# XcvrTestWiring.net
KiCad netlist of a schematic drawn in EAGLE
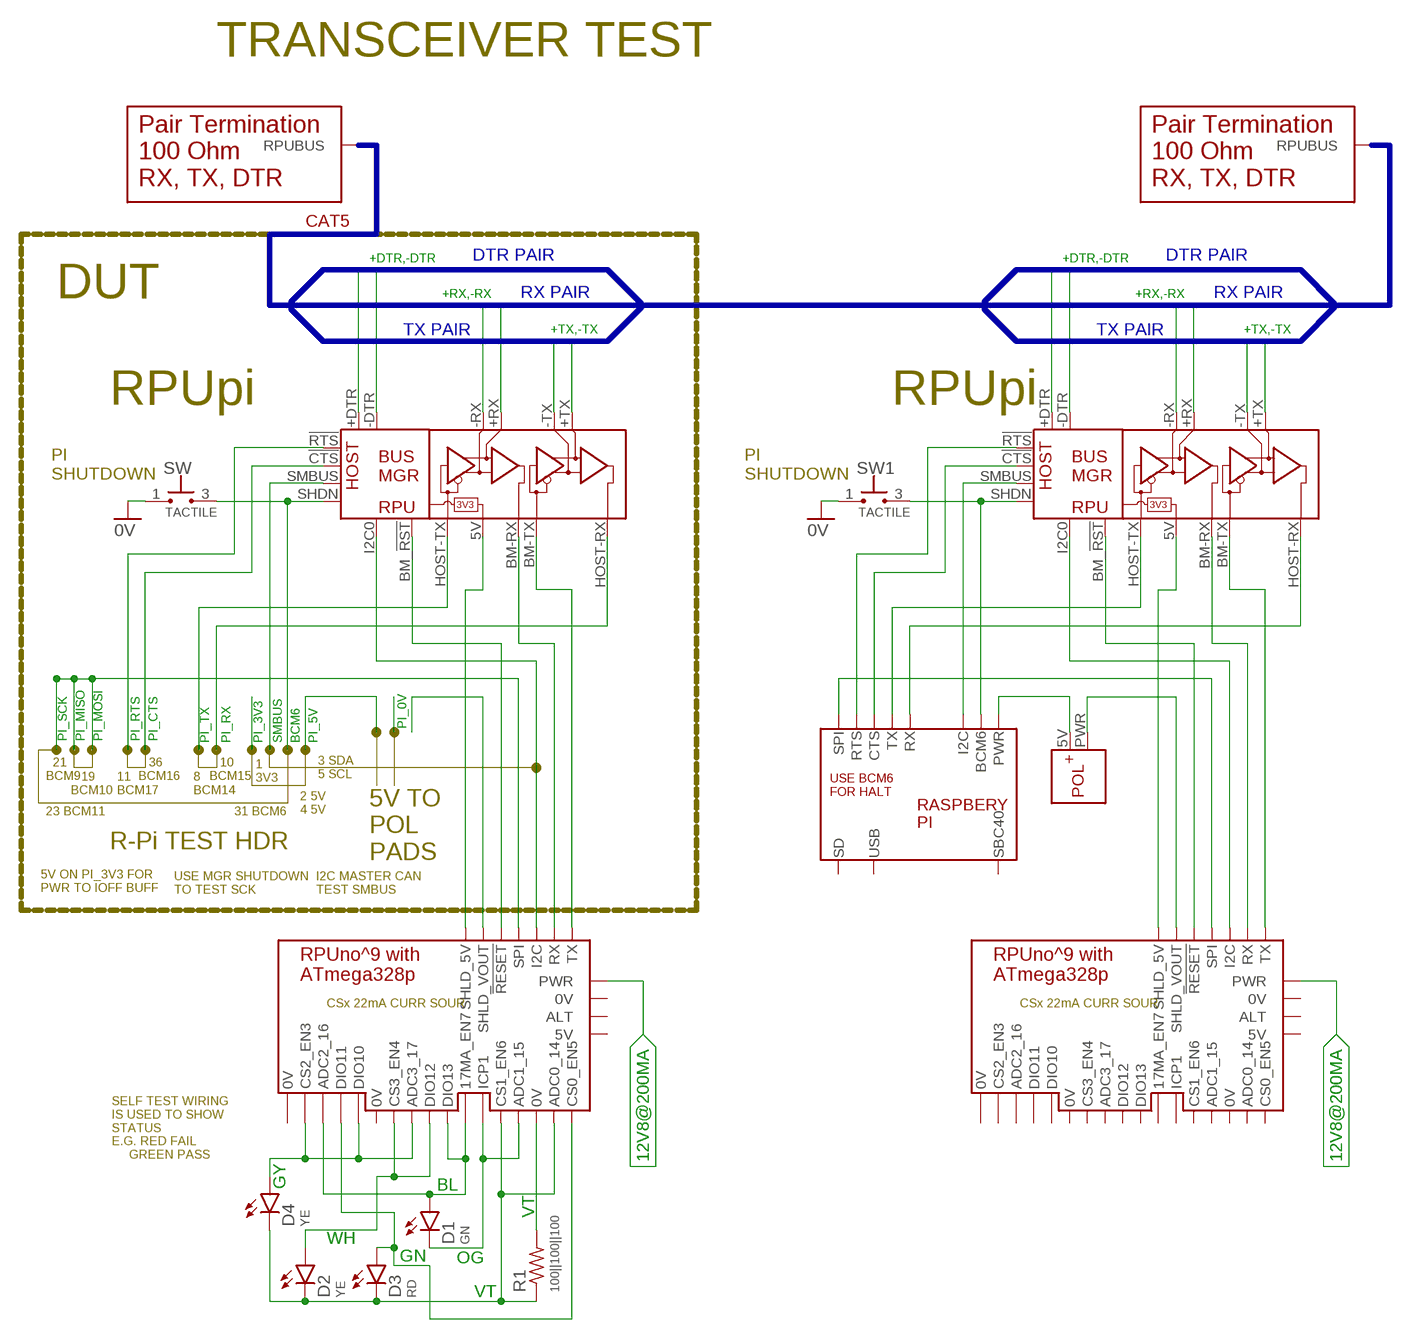
[diagram p0: schematic, sheet 1]

(export (version "E")
  (design (tool "Eeschema 10.0.6"))
  (components
    (comp (ref "BM1")
      (value "RPUNO")
      (footprint "eagle-import:NA-30")
      (libsource (lib "eagle-import") (part "RPUNO"))
    )
    (comp (ref "BM3")
      (value "RPUNO")
      (footprint "eagle-import:NA-30")
      (libsource (lib "eagle-import") (part "RPUNO"))
    )
    (comp (ref "D1")
      (value "GN")
      (footprint "eagle-import:LED5MM")
      (libsource (lib "eagle-import") (part "LED5MM"))
    )
    (comp (ref "D2")
      (value "YE")
      (footprint "eagle-import:LED5MM")
      (libsource (lib "eagle-import") (part "LED5MM"))
    )
    (comp (ref "D3")
      (value "RD")
      (footprint "eagle-import:LED5MM")
      (libsource (lib "eagle-import") (part "LED5MM"))
    )
    (comp (ref "D4")
      (value "YE")
      (footprint "eagle-import:LED5MM")
      (libsource (lib "eagle-import") (part "LED5MM"))
    )
    (comp (ref "R1")
      (value "100||100||100")
      (footprint "eagle-import:C0805(2012)")
      (libsource (lib "eagle-import") (part "R0805"))
    )
    (comp (ref "SW")
      (value "TACTILE")
      (footprint "eagle-import:KS11")
      (libsource (lib "eagle-import") (part "TAC_SW"))
    )
    (comp (ref "SW1")
      (value "TACTILE")
      (footprint "eagle-import:KS11")
      (libsource (lib "eagle-import") (part "TAC_SW"))
    )
    (comp (ref "U$1")
      (value "TERM")
      (footprint "eagle-import:NA-30")
      (libsource (lib "eagle-import") (part "TERM"))
    )
    (comp (ref "U$2")
      (value "BUS_MGR")
      (footprint "eagle-import:WITH_RPU_NAMES")
      (libsource (lib "eagle-import") (part "BUS_MGR"))
    )
    (comp (ref "U$3")
      (value "TERM")
      (footprint "eagle-import:NA-30")
      (libsource (lib "eagle-import") (part "TERM"))
    )
    (comp (ref "U$4")
      (value "PI")
      (footprint "eagle-import:NA-30")
      (libsource (lib "eagle-import") (part "PI"))
    )
    (comp (ref "U$5")
      (value "POL")
      (footprint "eagle-import:WITH_RPU_NAMES")
      (libsource (lib "eagle-import") (part "POL"))
    )
    (comp (ref "U$8")
      (value "BUS_MGR")
      (footprint "eagle-import:WITH_RPU_NAMES")
      (libsource (lib "eagle-import") (part "BUS_MGR"))
    )
  )
  (nets
    (net (code "2") (name "/+DTR") (class "Default")
      (node (ref "U$2") (pin "+DTR") (pinfunction "+DTR_+DTR") (pintype "bidirectional"))
      (node (ref "U$8") (pin "+DTR") (pinfunction "+DTR_+DTR") (pintype "bidirectional"))
    )
    (net (code "3") (name "/+RX") (class "Default")
      (node (ref "U$2") (pin "+RX") (pinfunction "+RX_+RX") (pintype "bidirectional"))
      (node (ref "U$8") (pin "+RX") (pinfunction "+RX_+RX") (pintype "bidirectional"))
    )
    (net (code "4") (name "/+TX") (class "Default")
      (node (ref "U$2") (pin "+TX") (pinfunction "+TX_+TX") (pintype "bidirectional"))
      (node (ref "U$8") (pin "+TX") (pinfunction "+TX_+TX") (pintype "bidirectional"))
    )
    (net (code "5") (name "/-DTR") (class "Default")
      (node (ref "U$2") (pin "-DTR") (pinfunction "-DTR_-DTR") (pintype "bidirectional"))
      (node (ref "U$8") (pin "-DTR") (pinfunction "-DTR_-DTR") (pintype "bidirectional"))
    )
    (net (code "6") (name "/-RX") (class "Default")
      (node (ref "U$2") (pin "-RX") (pinfunction "-RX_-RX") (pintype "bidirectional"))
      (node (ref "U$8") (pin "-RX") (pinfunction "-RX_-RX") (pintype "bidirectional"))
    )
    (net (code "7") (name "/-TX") (class "Default")
      (node (ref "U$2") (pin "-TX") (pinfunction "-TX_-TX") (pintype "bidirectional"))
      (node (ref "U$8") (pin "-TX") (pinfunction "-TX_-TX") (pintype "bidirectional"))
    )
    (net (code "8") (name "/BCM6") (class "Default")
      (node (ref "SW") (pin "3") (pinfunction "3_3") (pintype "passive"))
      (node (ref "SW1") (pin "3") (pinfunction "3_3") (pintype "passive"))
      (node (ref "U$2") (pin "SHDN") (pinfunction "SHDN_SHDN") (pintype "bidirectional"))
      (node (ref "U$4") (pin "7") (pinfunction "BCM6_7") (pintype "bidirectional"))
      (node (ref "U$8") (pin "SHDN") (pinfunction "SHDN_SHDN") (pintype "bidirectional"))
    )
    (net (code "9") (name "/BL") (class "Default")
      (node (ref "BM3") (pin "13") (pinfunction "ADC2_16_13") (pintype "bidirectional"))
      (node (ref "BM3") (pin "18") (pinfunction "DIO13_18") (pintype "bidirectional"))
      (node (ref "BM3") (pin "21") (pinfunction "17MA_EN7_21") (pintype "bidirectional"))
      (node (ref "D1") (pin "A") (pinfunction "A_A") (pintype "passive"))
    )
    (net (code "10") (name "/GN") (class "Default")
      (node (ref "BM3") (pin "14") (pinfunction "DIO11_14") (pintype "bidirectional"))
      (node (ref "BM3") (pin "23") (pinfunction "CS0_EN5_23") (pintype "bidirectional"))
      (node (ref "D3") (pin "A") (pinfunction "A_A") (pintype "passive"))
    )
    (net (code "11") (name "/GY") (class "Default")
      (node (ref "BM3") (pin "15") (pinfunction "DIO10_15") (pintype "bidirectional"))
      (node (ref "BM3") (pin "16") (pinfunction "ADC3_17_16") (pintype "bidirectional"))
      (node (ref "BM3") (pin "24") (pinfunction "CS2_EN3_24") (pintype "bidirectional"))
      (node (ref "D4") (pin "A") (pinfunction "A_A") (pintype "passive"))
    )
    (net (code "12") (name "/OG") (class "Default")
      (node (ref "BM3") (pin "10") (pinfunction "ADC1_15_10") (pintype "bidirectional"))
      (node (ref "BM3") (pin "12") (pinfunction "ICP1_12") (pintype "bidirectional"))
      (node (ref "D1") (pin "K") (pinfunction "K_K") (pintype "passive"))
    )
    (net (code "15") (name "/PI_5V") (class "Default")
      (node (ref "U$4") (pin "12") (pinfunction "PWR_12") (pintype "bidirectional"))
      (node (ref "U$5") (pin "5V") (pinfunction "5V_5V") (pintype "bidirectional"))
    )
    (net (code "16") (name "/PI_CTS") (class "Default")
      (node (ref "U$2") (pin "!CTS") (pinfunction "~{CTS}_!CTS") (pintype "bidirectional"))
      (node (ref "U$4") (pin "1") (pinfunction "CTS_1") (pintype "input"))
      (node (ref "U$8") (pin "!CTS") (pinfunction "~{CTS}_!CTS") (pintype "bidirectional"))
    )
    (net (code "18") (name "/PI_MOSI") (class "Default")
      (node (ref "BM1") (pin "4") (pinfunction "SPI_4") (pintype "bidirectional"))
      (node (ref "BM3") (pin "4") (pinfunction "SPI_4") (pintype "bidirectional"))
      (node (ref "U$4") (pin "10") (pinfunction "SPI_10") (pintype "bidirectional"))
    )
    (net (code "19") (name "/PI_RTS") (class "Default")
      (node (ref "U$2") (pin "!RTS") (pinfunction "~{RTS}_!RTS") (pintype "bidirectional"))
      (node (ref "U$4") (pin "2") (pinfunction "RTS_2") (pintype "input"))
      (node (ref "U$8") (pin "!RTS") (pinfunction "~{RTS}_!RTS") (pintype "bidirectional"))
    )
    (net (code "20") (name "/PI_RX") (class "Default")
      (node (ref "U$2") (pin "HOST-RX") (pinfunction "HOST_RX_HOST-RX") (pintype "bidirectional"))
      (node (ref "U$4") (pin "3") (pinfunction "RX_3") (pintype "bidirectional"))
      (node (ref "U$8") (pin "HOST-RX") (pinfunction "HOST_RX_HOST-RX") (pintype "bidirectional"))
    )
    (net (code "22") (name "/PI_TX") (class "Default")
      (node (ref "U$2") (pin "HOST-TX") (pinfunction "HOST_TX_HOST-TX") (pintype "bidirectional"))
      (node (ref "U$4") (pin "4") (pinfunction "TX_4") (pintype "bidirectional"))
      (node (ref "U$8") (pin "HOST-TX") (pinfunction "HOST_TX_HOST-TX") (pintype "bidirectional"))
    )
    (net (code "23") (name "/SMBUS") (class "Default")
      (node (ref "U$2") (pin "SMBUS") (pinfunction "SMBUS_SMBUS") (pintype "bidirectional"))
      (node (ref "U$4") (pin "8") (pinfunction "I2C_8") (pintype "bidirectional"))
      (node (ref "U$8") (pin "SMBUS") (pinfunction "SMBUS_SMBUS") (pintype "bidirectional"))
    )
    (net (code "24") (name "/VT") (class "Default")
      (node (ref "BM3") (pin "11") (pinfunction "ADC0_14_11") (pintype "bidirectional"))
      (node (ref "BM3") (pin "22") (pinfunction "CS1_EN6_22") (pintype "bidirectional"))
      (node (ref "D2") (pin "K") (pinfunction "K_K") (pintype "passive"))
      (node (ref "D3") (pin "K") (pinfunction "K_K") (pintype "passive"))
      (node (ref "D4") (pin "K") (pinfunction "K_K") (pintype "passive"))
      (node (ref "R1") (pin "1") (pinfunction "1_1") (pintype "passive"))
    )
    (net (code "25") (name "/WH") (class "Default")
      (node (ref "BM3") (pin "17") (pinfunction "DIO12_17") (pintype "bidirectional"))
      (node (ref "BM3") (pin "29") (pinfunction "CS3_EN4_29") (pintype "bidirectional"))
      (node (ref "D2") (pin "A") (pinfunction "A_A") (pintype "passive"))
    )
    (net (code "29") (name "/{B$2}") (class "Default")
      (node (ref "U$3") (pin "1") (pinfunction "RPUBUS_1") (pintype "bidirectional"))
    )
    (net (code "30") (name "0V") (class "Default")
      (node (ref "SW") (pin "1") (pinfunction "1_1") (pintype "passive"))
      (node (ref "SW1") (pin "1") (pinfunction "1_1") (pintype "passive"))
    )
    (net (code "31") (name "12V8@200MA") (class "Default")
      (node (ref "BM1") (pin "8") (pinfunction "PWR_8") (pintype "bidirectional"))
      (node (ref "BM3") (pin "8") (pinfunction "PWR_8") (pintype "bidirectional"))
    )
    (net (code "32") (name "Net-(BM1-I2C)") (class "Default")
      (node (ref "BM1") (pin "3") (pinfunction "I2C_3") (pintype "bidirectional"))
      (node (ref "U$2") (pin "I2C0") (pinfunction "I2C0_I2C0") (pintype "bidirectional"))
    )
    (net (code "33") (name "Net-(BM1-RX)") (class "Default")
      (node (ref "BM1") (pin "2") (pinfunction "RX_2") (pintype "bidirectional"))
      (node (ref "U$2") (pin "BM-RX") (pinfunction "BM_RX_BM-RX") (pintype "bidirectional"))
    )
    (net (code "34") (name "Net-(BM1-SHLD_5V)") (class "Default")
      (node (ref "BM1") (pin "6") (pinfunction "SHLD_5V_6") (pintype "bidirectional"))
      (node (ref "U$2") (pin "5V") (pinfunction "PWR_5V") (pintype "bidirectional"))
    )
    (net (code "35") (name "Net-(BM1-SHLD_VOUT)") (class "Default")
      (node (ref "BM1") (pin "7") (pinfunction "SHLD_VOUT_7") (pintype "bidirectional"))
      (node (ref "U$5") (pin "PWR") (pinfunction "VIN_PWR") (pintype "bidirectional"))
    )
    (net (code "36") (name "Net-(BM1-TX)") (class "Default")
      (node (ref "BM1") (pin "1") (pinfunction "TX_1") (pintype "bidirectional"))
      (node (ref "U$2") (pin "BM-TX") (pinfunction "BM_TX_BM-TX") (pintype "bidirectional"))
    )
    (net (code "37") (name "Net-(BM1-~{RESET})") (class "Default")
      (node (ref "BM1") (pin "5") (pinfunction "~{RESET}_5") (pintype "bidirectional"))
      (node (ref "U$2") (pin "BM_!RST!") (pinfunction "BM-~{RST}_BM_!RST!") (pintype "bidirectional"))
    )
    (net (code "38") (name "Net-(BM3-0V-Pad26)") (class "Default")
      (node (ref "BM3") (pin "26") (pinfunction "0V_26") (pintype "bidirectional"))
      (node (ref "R1") (pin "2") (pinfunction "2_2") (pintype "passive"))
    )
    (net (code "39") (name "Net-(BM3-I2C)") (class "Default")
      (node (ref "BM3") (pin "3") (pinfunction "I2C_3") (pintype "bidirectional"))
      (node (ref "U$8") (pin "I2C0") (pinfunction "I2C0_I2C0") (pintype "bidirectional"))
    )
    (net (code "40") (name "Net-(BM3-RX)") (class "Default")
      (node (ref "BM3") (pin "2") (pinfunction "RX_2") (pintype "bidirectional"))
      (node (ref "U$8") (pin "BM-RX") (pinfunction "BM_RX_BM-RX") (pintype "bidirectional"))
    )
    (net (code "41") (name "Net-(BM3-SHLD_5V)") (class "Default")
      (node (ref "BM3") (pin "6") (pinfunction "SHLD_5V_6") (pintype "bidirectional"))
      (node (ref "U$8") (pin "5V") (pinfunction "PWR_5V") (pintype "bidirectional"))
    )
    (net (code "42") (name "Net-(BM3-TX)") (class "Default")
      (node (ref "BM3") (pin "1") (pinfunction "TX_1") (pintype "bidirectional"))
      (node (ref "U$8") (pin "BM-TX") (pinfunction "BM_TX_BM-TX") (pintype "bidirectional"))
    )
    (net (code "43") (name "Net-(BM3-~{RESET})") (class "Default")
      (node (ref "BM3") (pin "5") (pinfunction "~{RESET}_5") (pintype "bidirectional"))
      (node (ref "U$8") (pin "BM_!RST!") (pinfunction "BM-~{RST}_BM_!RST!") (pintype "bidirectional"))
    )
    (net (code "44") (name "unconnected-(BM1-0V-Pad9)") (class "Default")
      (node (ref "BM1") (pin "9") (pinfunction "0V_9") (pintype "bidirectional"))
    )
    (net (code "45") (name "unconnected-(BM1-0V-Pad26)") (class "Default")
      (node (ref "BM1") (pin "26") (pinfunction "0V_26") (pintype "bidirectional"))
    )
    (net (code "46") (name "unconnected-(BM1-0V-Pad27)") (class "Default")
      (node (ref "BM1") (pin "27") (pinfunction "0V_27") (pintype "bidirectional"))
    )
    (net (code "47") (name "unconnected-(BM1-0V-Pad28)") (class "Default")
      (node (ref "BM1") (pin "28") (pinfunction "0V_28") (pintype "bidirectional"))
    )
    (net (code "48") (name "unconnected-(BM1-5V-Pad19)") (class "Default")
      (node (ref "BM1") (pin "19") (pinfunction "5V_19") (pintype "bidirectional"))
    )
    (net (code "49") (name "unconnected-(BM1-17MA_EN7-Pad21)") (class "Default")
      (node (ref "BM1") (pin "21") (pinfunction "17MA_EN7_21") (pintype "bidirectional"))
    )
    (net (code "50") (name "unconnected-(BM1-ADC0_14-Pad11)") (class "Default")
      (node (ref "BM1") (pin "11") (pinfunction "ADC0_14_11") (pintype "bidirectional"))
    )
    (net (code "51") (name "unconnected-(BM1-ADC1_15-Pad10)") (class "Default")
      (node (ref "BM1") (pin "10") (pinfunction "ADC1_15_10") (pintype "bidirectional"))
    )
    (net (code "52") (name "unconnected-(BM1-ADC2_16-Pad13)") (class "Default")
      (node (ref "BM1") (pin "13") (pinfunction "ADC2_16_13") (pintype "bidirectional"))
    )
    (net (code "53") (name "unconnected-(BM1-ADC3_17-Pad16)") (class "Default")
      (node (ref "BM1") (pin "16") (pinfunction "ADC3_17_16") (pintype "bidirectional"))
    )
    (net (code "54") (name "unconnected-(BM1-ALT-Pad20)") (class "Default")
      (node (ref "BM1") (pin "20") (pinfunction "ALT_20") (pintype "bidirectional"))
    )
    (net (code "55") (name "unconnected-(BM1-CS0_EN5-Pad23)") (class "Default")
      (node (ref "BM1") (pin "23") (pinfunction "CS0_EN5_23") (pintype "bidirectional"))
    )
    (net (code "56") (name "unconnected-(BM1-CS1_EN6-Pad22)") (class "Default")
      (node (ref "BM1") (pin "22") (pinfunction "CS1_EN6_22") (pintype "bidirectional"))
    )
    (net (code "57") (name "unconnected-(BM1-CS2_EN3-Pad24)") (class "Default")
      (node (ref "BM1") (pin "24") (pinfunction "CS2_EN3_24") (pintype "bidirectional"))
    )
    (net (code "58") (name "unconnected-(BM1-CS3_EN4-Pad29)") (class "Default")
      (node (ref "BM1") (pin "29") (pinfunction "CS3_EN4_29") (pintype "bidirectional"))
    )
    (net (code "59") (name "unconnected-(BM1-DIO10-Pad15)") (class "Default")
      (node (ref "BM1") (pin "15") (pinfunction "DIO10_15") (pintype "bidirectional"))
    )
    (net (code "60") (name "unconnected-(BM1-DIO11-Pad14)") (class "Default")
      (node (ref "BM1") (pin "14") (pinfunction "DIO11_14") (pintype "bidirectional"))
    )
    (net (code "61") (name "unconnected-(BM1-DIO12-Pad17)") (class "Default")
      (node (ref "BM1") (pin "17") (pinfunction "DIO12_17") (pintype "bidirectional"))
    )
    (net (code "62") (name "unconnected-(BM1-DIO13-Pad18)") (class "Default")
      (node (ref "BM1") (pin "18") (pinfunction "DIO13_18") (pintype "bidirectional"))
    )
    (net (code "63") (name "unconnected-(BM1-ICP1-Pad12)") (class "Default")
      (node (ref "BM1") (pin "12") (pinfunction "ICP1_12") (pintype "bidirectional"))
    )
    (net (code "64") (name "unconnected-(BM3-0V-Pad9)") (class "Default")
      (node (ref "BM3") (pin "9") (pinfunction "0V_9") (pintype "bidirectional"))
    )
    (net (code "65") (name "unconnected-(BM3-0V-Pad27)") (class "Default")
      (node (ref "BM3") (pin "27") (pinfunction "0V_27") (pintype "bidirectional"))
    )
    (net (code "66") (name "unconnected-(BM3-0V-Pad28)") (class "Default")
      (node (ref "BM3") (pin "28") (pinfunction "0V_28") (pintype "bidirectional"))
    )
    (net (code "67") (name "unconnected-(BM3-5V-Pad19)") (class "Default")
      (node (ref "BM3") (pin "19") (pinfunction "5V_19") (pintype "bidirectional"))
    )
    (net (code "68") (name "unconnected-(BM3-ALT-Pad20)") (class "Default")
      (node (ref "BM3") (pin "20") (pinfunction "ALT_20") (pintype "bidirectional"))
    )
    (net (code "69") (name "unconnected-(BM3-SHLD_VOUT-Pad7)") (class "Default")
      (node (ref "BM3") (pin "7") (pinfunction "SHLD_VOUT_7") (pintype "bidirectional"))
    )
    (net (code "70") (name "unconnected-(U$1-RPUBUS-Pad1)") (class "Default")
      (node (ref "U$1") (pin "1") (pinfunction "RPUBUS_1") (pintype "bidirectional"))
    )
    (net (code "71") (name "unconnected-(U$4-SBC40-Pad5)") (class "Default")
      (node (ref "U$4") (pin "5") (pinfunction "SBC40_5") (pintype "input"))
    )
    (net (code "72") (name "unconnected-(U$4-SD-Pad9)") (class "Default")
      (node (ref "U$4") (pin "9") (pinfunction "SD_9") (pintype "input"))
    )
    (net (code "73") (name "unconnected-(U$4-USB-Pad11)") (class "Default")
      (node (ref "U$4") (pin "11") (pinfunction "USB_11") (pintype "input"))
    )
  )
)
